# IR_BEACON.net
KiCad netlist of a schematic drawn in EAGLE
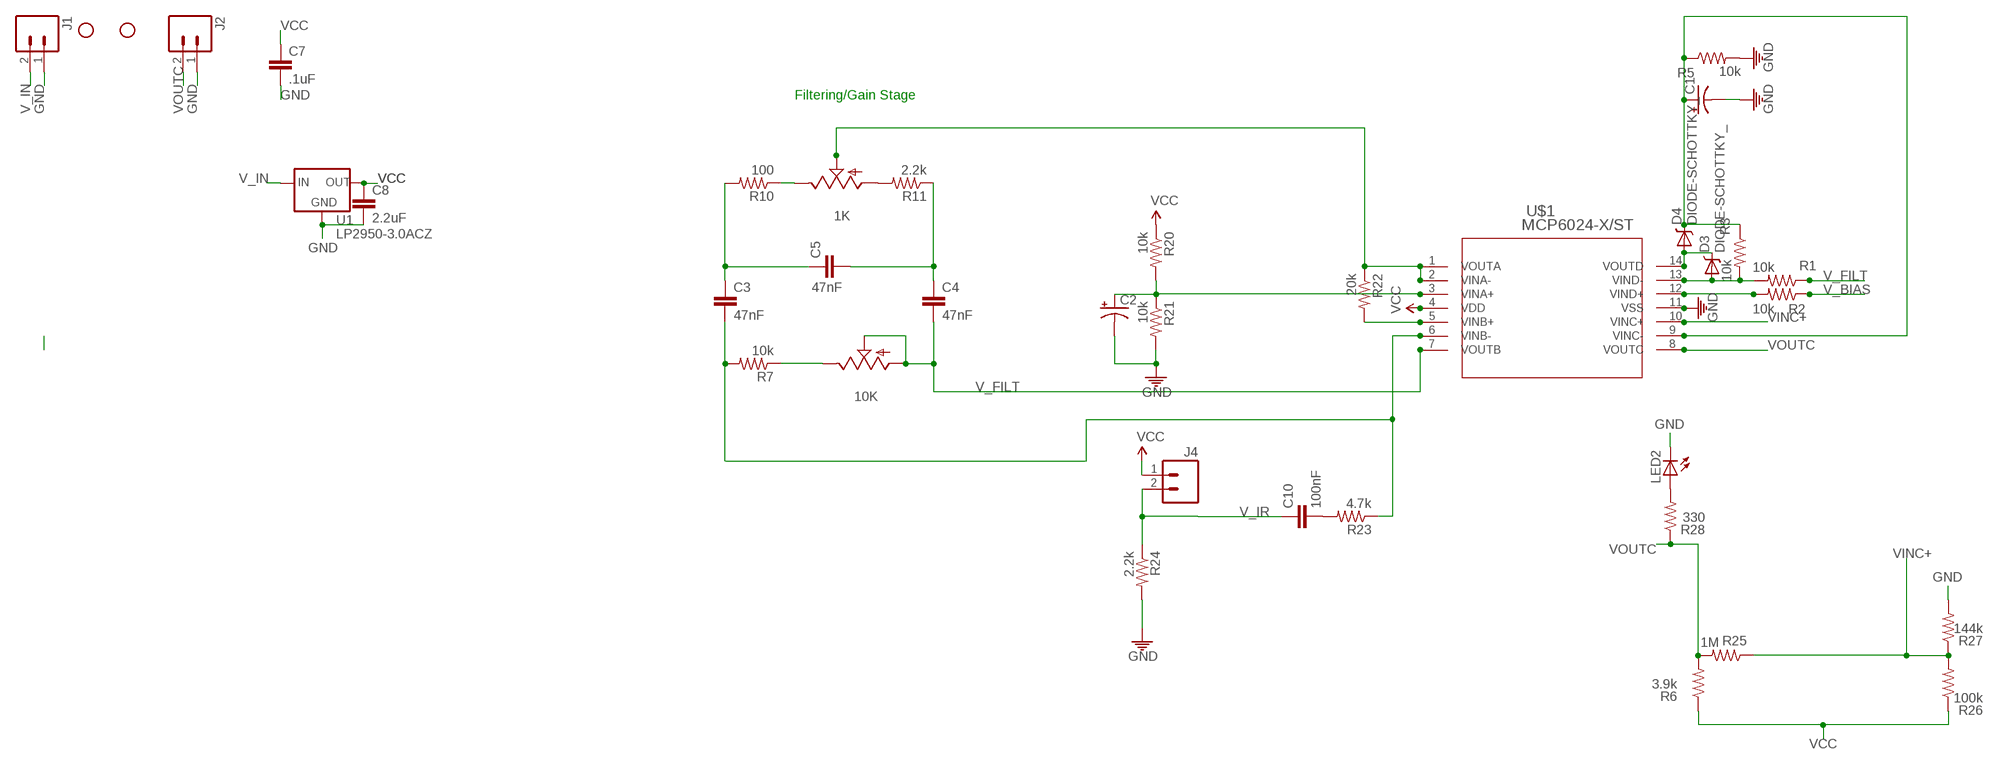
[diagram p0: schematic, sheet 1]

(export (version "E")
  (design (tool "Eeschema 10.0.6"))
  (components
    (comp (ref "1K")
      (value "TRIM_US-S64W")
      (footprint "eagle-import:S64W")
      (libsource (lib "eagle-import") (part "TRIM_US-S64W"))
    )
    (comp (ref "10K")
      (value "TRIM_US-S64W")
      (footprint "eagle-import:S64W")
      (libsource (lib "eagle-import") (part "TRIM_US-S64W"))
    )
    (comp (ref "C1")
      (value "CAP_POLPTH2")
      (footprint "eagle-import:CPOL-RADIAL-10UF-25V")
      (libsource (lib "eagle-import") (part "CAP_POLPTH2"))
    )
    (comp (ref "C2")
      (value "CAP_POLPTH2")
      (footprint "eagle-import:CPOL-RADIAL-10UF-25V")
      (libsource (lib "eagle-import") (part "CAP_POLPTH2"))
    )
    (comp (ref "C3")
      (value "47nF")
      (footprint "eagle-import:1206")
      (libsource (lib "eagle-import") (part "CAP1206"))
    )
    (comp (ref "C4")
      (value "47nF")
      (footprint "eagle-import:1206")
      (libsource (lib "eagle-import") (part "CAP1206"))
    )
    (comp (ref "C5")
      (value "47nF")
      (footprint "eagle-import:1206")
      (libsource (lib "eagle-import") (part "CAP1206"))
    )
    (comp (ref "C7")
      (value ".1uF")
      (footprint "eagle-import:0805")
      (libsource (lib "eagle-import") (part "CAP0805"))
    )
    (comp (ref "C8")
      (value "2.2uF")
      (footprint "eagle-import:0805")
      (libsource (lib "eagle-import") (part "CAP0805"))
    )
    (comp (ref "C10")
      (value "100nF")
      (footprint "eagle-import:0805")
      (libsource (lib "eagle-import") (part "CAP0805"))
    )
    (comp (ref "D3")
      (value "DIODE-SCHOTTKY_")
      (footprint "eagle-import:SMA-DIODE")
      (libsource (lib "eagle-import") (part "DIODE-SCHOTTKY_"))
    )
    (comp (ref "D4")
      (value "DIODE-SCHOTTKY_")
      (footprint "eagle-import:SMA-DIODE")
      (libsource (lib "eagle-import") (part "DIODE-SCHOTTKY_"))
    )
    (comp (ref "J1")
      (value "M02LOCK")
      (footprint "eagle-import:1X02_LOCK")
      (libsource (lib "eagle-import") (part "M02LOCK"))
    )
    (comp (ref "J2")
      (value "M02LOCK")
      (footprint "eagle-import:1X02_LOCK")
      (libsource (lib "eagle-import") (part "M02LOCK"))
    )
    (comp (ref "J4")
      (value "M02LOCK")
      (footprint "eagle-import:1X02_LOCK")
      (libsource (lib "eagle-import") (part "M02LOCK"))
    )
    (comp (ref "JP3")
      (value "STAND-OFFTIGHT")
      (footprint "eagle-import:STAND-OFF-TIGHT")
      (libsource (lib "eagle-import") (part "STAND-OFFTIGHT"))
    )
    (comp (ref "JP5")
      (value "STAND-OFFTIGHT")
      (footprint "eagle-import:STAND-OFF-TIGHT")
      (libsource (lib "eagle-import") (part "STAND-OFFTIGHT"))
    )
    (comp (ref "LED2")
      (value "LED1206")
      (footprint "eagle-import:LED-1206")
      (libsource (lib "eagle-import") (part "LED1206"))
    )
    (comp (ref "R1")
      (value "10k")
      (footprint "eagle-import:0805")
      (libsource (lib "eagle-import") (part "RESISTOR0805-RES"))
    )
    (comp (ref "R2")
      (value "10k")
      (footprint "eagle-import:0805")
      (libsource (lib "eagle-import") (part "RESISTOR0805-RES"))
    )
    (comp (ref "R3")
      (value "10k")
      (footprint "eagle-import:0805")
      (libsource (lib "eagle-import") (part "RESISTOR0805-RES"))
    )
    (comp (ref "R5")
      (value "10k")
      (footprint "eagle-import:0805")
      (libsource (lib "eagle-import") (part "RESISTOR0805-RES"))
    )
    (comp (ref "R6")
      (value "3.9k")
      (footprint "eagle-import:0805")
      (libsource (lib "eagle-import") (part "RESISTOR0805-RES"))
    )
    (comp (ref "R7")
      (value "10k")
      (footprint "eagle-import:0805")
      (libsource (lib "eagle-import") (part "RESISTOR0805-RES"))
    )
    (comp (ref "R10")
      (value "100")
      (footprint "eagle-import:0805")
      (libsource (lib "eagle-import") (part "RESISTOR0805-RES"))
    )
    (comp (ref "R11")
      (value "2.2k")
      (footprint "eagle-import:0805")
      (libsource (lib "eagle-import") (part "RESISTOR0805-RES"))
    )
    (comp (ref "R20")
      (value "10k")
      (footprint "eagle-import:0805")
      (libsource (lib "eagle-import") (part "RESISTOR0805-RES"))
    )
    (comp (ref "R21")
      (value "10k")
      (footprint "eagle-import:0805")
      (libsource (lib "eagle-import") (part "RESISTOR0805-RES"))
    )
    (comp (ref "R22")
      (value "20k")
      (footprint "eagle-import:0805")
      (libsource (lib "eagle-import") (part "RESISTOR0805-RES"))
    )
    (comp (ref "R23")
      (value "4.7k")
      (footprint "eagle-import:0805")
      (libsource (lib "eagle-import") (part "RESISTOR0805-RES"))
    )
    (comp (ref "R24")
      (value "2.2k")
      (footprint "eagle-import:0805")
      (libsource (lib "eagle-import") (part "RESISTOR0805-RES"))
    )
    (comp (ref "R25")
      (value "1M")
      (footprint "eagle-import:0805")
      (libsource (lib "eagle-import") (part "RESISTOR0805-RES"))
    )
    (comp (ref "R26")
      (value "100k")
      (footprint "eagle-import:0805")
      (libsource (lib "eagle-import") (part "RESISTOR0805-RES"))
    )
    (comp (ref "R27")
      (value "144k")
      (footprint "eagle-import:0805")
      (libsource (lib "eagle-import") (part "RESISTOR0805-RES"))
    )
    (comp (ref "R28")
      (value "330")
      (footprint "eagle-import:0805")
      (libsource (lib "eagle-import") (part "RESISTOR0805-RES"))
    )
    (comp (ref "U$1")
      (value "MCP6024-X/ST")
      (footprint "eagle-import:TSSOP14_MC")
      (libsource (lib "eagle-import") (part "MCP6024-X/ST"))
    )
    (comp (ref "U1")
      (value "LP2950-3.0ACZ")
      (footprint "eagle-import:TO92")
      (libsource (lib "eagle-import") (part "LP2950ACZ-3.0"))
    )
  )
  (nets
    (net (code "1") (name "/VINC+") (class "Default")
      (node (ref "R25") (pin "1") (pinfunction "1_1") (pintype "passive"))
      (node (ref "R26") (pin "2") (pinfunction "2_2") (pintype "passive"))
      (node (ref "R27") (pin "1") (pinfunction "1_1") (pintype "passive"))
      (node (ref "U$1") (pin "10") (pinfunction "VINC+_10") (pintype "passive"))
    )
    (net (code "2") (name "/VOUTC") (class "Default")
      (node (ref "J2") (pin "2") (pinfunction "1_2") (pintype "passive"))
      (node (ref "R25") (pin "2") (pinfunction "2_2") (pintype "passive"))
      (node (ref "R28") (pin "1") (pinfunction "1_1") (pintype "passive"))
      (node (ref "R6") (pin "2") (pinfunction "2_2") (pintype "passive"))
      (node (ref "U$1") (pin "8") (pinfunction "VOUTC_8") (pintype "passive"))
    )
    (net (code "3") (name "/V_BIAS") (class "Default")
      (node (ref "1K") (pin "S") (pinfunction "S_S") (pintype "passive"))
      (node (ref "R2") (pin "2") (pinfunction "2_2") (pintype "passive"))
      (node (ref "R22") (pin "1") (pinfunction "1_1") (pintype "passive"))
      (node (ref "U$1") (pin "1") (pinfunction "VOUTA_1") (pintype "passive"))
      (node (ref "U$1") (pin "12") (pinfunction "VIND+_12") (pintype "passive"))
      (node (ref "U$1") (pin "2") (pinfunction "VINA-_2") (pintype "passive"))
    )
    (net (code "4") (name "/V_FILT") (class "Default")
      (node (ref "10K") (pin "A") (pinfunction "A_A") (pintype "passive"))
      (node (ref "10K") (pin "S") (pinfunction "S_S") (pintype "passive"))
      (node (ref "C4") (pin "2") (pinfunction "2_2") (pintype "passive"))
      (node (ref "R1") (pin "1") (pinfunction "1_1") (pintype "passive"))
      (node (ref "U$1") (pin "7") (pinfunction "VOUTB_7") (pintype "passive"))
    )
    (net (code "5") (name "/V_IN") (class "Default")
      (node (ref "J1") (pin "2") (pinfunction "1_2") (pintype "passive"))
      (node (ref "U1") (pin "3") (pinfunction "IN_3") (pintype "input"))
    )
    (net (code "6") (name "/V_IR") (class "Default")
      (node (ref "C10") (pin "1") (pinfunction "1_1") (pintype "passive"))
      (node (ref "J4") (pin "2") (pinfunction "1_2") (pintype "passive"))
      (node (ref "R24") (pin "1") (pinfunction "1_1") (pintype "passive"))
    )
    (net (code "7") (name "GND") (class "Default")
      (node (ref "C1") (pin "2") (pinfunction "-_2") (pintype "passive"))
      (node (ref "C2") (pin "2") (pinfunction "-_2") (pintype "passive"))
      (node (ref "C7") (pin "2") (pinfunction "2_2") (pintype "passive"))
      (node (ref "C8") (pin "2") (pinfunction "2_2") (pintype "passive"))
      (node (ref "J1") (pin "1") (pinfunction "2_1") (pintype "passive"))
      (node (ref "J2") (pin "1") (pinfunction "2_1") (pintype "passive"))
      (node (ref "LED2") (pin "C") (pinfunction "C_C") (pintype "passive"))
      (node (ref "R21") (pin "2") (pinfunction "2_2") (pintype "passive"))
      (node (ref "R24") (pin "2") (pinfunction "2_2") (pintype "passive"))
      (node (ref "R27") (pin "2") (pinfunction "2_2") (pintype "passive"))
      (node (ref "R5") (pin "2") (pinfunction "2_2") (pintype "passive"))
      (node (ref "U$1") (pin "11") (pinfunction "VSS_11") (pintype "passive"))
      (node (ref "U1") (pin "2") (pinfunction "GND_2") (pintype "input"))
    )
    (net (code "8") (name "Net-(1K-PadA)") (class "Default")
      (node (ref "1K") (pin "A") (pinfunction "A_A") (pintype "passive"))
      (node (ref "R11") (pin "2") (pinfunction "2_2") (pintype "passive"))
    )
    (net (code "9") (name "Net-(1K-PadE)") (class "Default")
      (node (ref "1K") (pin "E") (pinfunction "E_E") (pintype "passive"))
      (node (ref "R10") (pin "1") (pinfunction "1_1") (pintype "passive"))
    )
    (net (code "10") (name "Net-(10K-PadE)") (class "Default")
      (node (ref "10K") (pin "E") (pinfunction "E_E") (pintype "passive"))
      (node (ref "R7") (pin "1") (pinfunction "1_1") (pintype "passive"))
    )
    (net (code "11") (name "Net-(C1-+)") (class "Default")
      (node (ref "C1") (pin "1") (pinfunction "+_1") (pintype "passive"))
      (node (ref "D4") (pin "C") (pinfunction "C_C") (pintype "passive"))
      (node (ref "R3") (pin "1") (pinfunction "1_1") (pintype "passive"))
      (node (ref "R5") (pin "1") (pinfunction "1_1") (pintype "passive"))
      (node (ref "U$1") (pin "9") (pinfunction "VINC-_9") (pintype "passive"))
    )
    (net (code "12") (name "Net-(C2-+)") (class "Default")
      (node (ref "C2") (pin "1") (pinfunction "+_1") (pintype "passive"))
      (node (ref "R20") (pin "2") (pinfunction "2_2") (pintype "passive"))
      (node (ref "R21") (pin "1") (pinfunction "1_1") (pintype "passive"))
      (node (ref "U$1") (pin "3") (pinfunction "VINA+_3") (pintype "passive"))
    )
    (net (code "13") (name "Net-(C3-Pad1)") (class "Default")
      (node (ref "C3") (pin "1") (pinfunction "1_1") (pintype "passive"))
      (node (ref "C5") (pin "1") (pinfunction "1_1") (pintype "passive"))
      (node (ref "R10") (pin "2") (pinfunction "2_2") (pintype "passive"))
    )
    (net (code "14") (name "Net-(C4-Pad1)") (class "Default")
      (node (ref "C4") (pin "1") (pinfunction "1_1") (pintype "passive"))
      (node (ref "C5") (pin "2") (pinfunction "2_2") (pintype "passive"))
      (node (ref "R11") (pin "1") (pinfunction "1_1") (pintype "passive"))
    )
    (net (code "15") (name "Net-(C10-Pad2)") (class "Default")
      (node (ref "C10") (pin "2") (pinfunction "2_2") (pintype "passive"))
      (node (ref "R23") (pin "2") (pinfunction "2_2") (pintype "passive"))
    )
    (net (code "16") (name "Net-(LED2-PadA)") (class "Default")
      (node (ref "LED2") (pin "A") (pinfunction "A_A") (pintype "passive"))
      (node (ref "R28") (pin "2") (pinfunction "2_2") (pintype "passive"))
    )
    (net (code "17") (name "Net-(U$1-VINB+)") (class "Default")
      (node (ref "R22") (pin "2") (pinfunction "2_2") (pintype "passive"))
      (node (ref "U$1") (pin "5") (pinfunction "VINB+_5") (pintype "passive"))
    )
    (net (code "18") (name "Net-(U$1-VINB-)") (class "Default")
      (node (ref "C3") (pin "2") (pinfunction "2_2") (pintype "passive"))
      (node (ref "R23") (pin "1") (pinfunction "1_1") (pintype "passive"))
      (node (ref "R7") (pin "2") (pinfunction "2_2") (pintype "passive"))
      (node (ref "U$1") (pin "6") (pinfunction "VINB-_6") (pintype "passive"))
    )
    (net (code "19") (name "Net-(U$1-VIND-)") (class "Default")
      (node (ref "D3") (pin "A") (pinfunction "A_A") (pintype "passive"))
      (node (ref "R1") (pin "2") (pinfunction "2_2") (pintype "passive"))
      (node (ref "R3") (pin "2") (pinfunction "2_2") (pintype "passive"))
      (node (ref "U$1") (pin "13") (pinfunction "VIND-_13") (pintype "passive"))
    )
    (net (code "20") (name "Net-(U$1-VOUTD)") (class "Default")
      (node (ref "D3") (pin "C") (pinfunction "C_C") (pintype "passive"))
      (node (ref "D4") (pin "A") (pinfunction "A_A") (pintype "passive"))
      (node (ref "U$1") (pin "14") (pinfunction "VOUTD_14") (pintype "passive"))
    )
    (net (code "21") (name "VCC") (class "Default")
      (node (ref "C7") (pin "1") (pinfunction "1_1") (pintype "passive"))
      (node (ref "C8") (pin "1") (pinfunction "1_1") (pintype "passive"))
      (node (ref "J4") (pin "1") (pinfunction "2_1") (pintype "passive"))
      (node (ref "R20") (pin "1") (pinfunction "1_1") (pintype "passive"))
      (node (ref "R26") (pin "1") (pinfunction "1_1") (pintype "passive"))
      (node (ref "R6") (pin "1") (pinfunction "1_1") (pintype "passive"))
      (node (ref "U$1") (pin "4") (pinfunction "VDD_4") (pintype "passive"))
      (node (ref "U1") (pin "1") (pinfunction "OUT_1") (pintype "passive"))
    )
    (net (code "22") (name "unconnected-(R2-Pad1)") (class "Default")
      (node (ref "R2") (pin "1") (pinfunction "1_1") (pintype "passive"))
    )
  )
)
